# semaforo.net
KiCad netlist of a schematic drawn in EAGLE
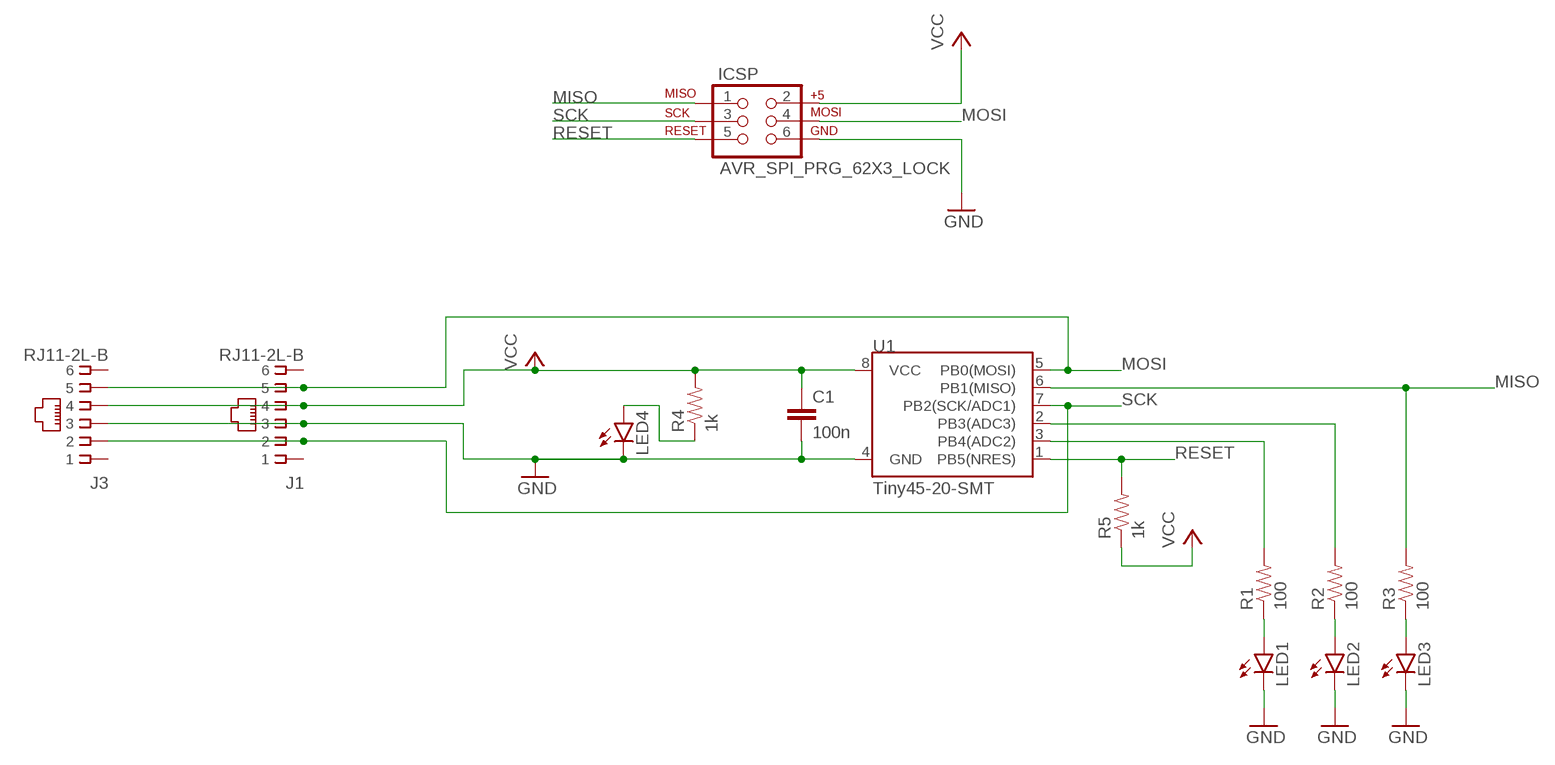
[diagram p0: schematic, sheet 1]

(export (version "E")
  (design (tool "Eeschema 10.0.6"))
  (components
    (comp (ref "C1")
      (value "100n")
      (footprint "eagle-import:1206")
      (libsource (lib "eagle-import") (part "CAP1206"))
    )
    (comp (ref "ICSP")
      (value "AVR_SPI_PRG_62X3_LOCK")
      (footprint "eagle-import:2X3_LOCK")
      (libsource (lib "eagle-import") (part "AVR_SPI_PRG_62X3_LOCK"))
    )
    (comp (ref "J1")
      (value "RJ11-2L-B")
      (footprint "eagle-import:RJ11-NO_SHIELD")
      (fields (field (name "MF") "TYCO ELECTRONICS"))
      (libsource (lib "eagle-import") (part "RJ11-2L-B"))
    )
    (comp (ref "J3")
      (value "RJ11-2L-B")
      (footprint "eagle-import:RJ11-NO_SHIELD")
      (fields (field (name "MF") "TYCO ELECTRONICS"))
      (libsource (lib "eagle-import") (part "RJ11-2L-B"))
    )
    (comp (ref "LED1")
      (value "LED5MM")
      (footprint "eagle-import:LED5MM")
      (libsource (lib "eagle-import") (part "LED5MM"))
    )
    (comp (ref "LED2")
      (value "LED5MM")
      (footprint "eagle-import:LED5MM")
      (libsource (lib "eagle-import") (part "LED5MM"))
    )
    (comp (ref "LED3")
      (value "LED5MM")
      (footprint "eagle-import:LED5MM")
      (libsource (lib "eagle-import") (part "LED5MM"))
    )
    (comp (ref "LED4")
      (value "LED1206")
      (footprint "eagle-import:LED-1206")
      (libsource (lib "eagle-import") (part "LED1206"))
    )
    (comp (ref "R1")
      (value "100")
      (footprint "eagle-import:1206")
      (libsource (lib "eagle-import") (part "RESISTOR1206"))
    )
    (comp (ref "R2")
      (value "100")
      (footprint "eagle-import:1206")
      (libsource (lib "eagle-import") (part "RESISTOR1206"))
    )
    (comp (ref "R3")
      (value "100")
      (footprint "eagle-import:1206")
      (libsource (lib "eagle-import") (part "RESISTOR1206"))
    )
    (comp (ref "R4")
      (value "1k")
      (footprint "eagle-import:1206")
      (libsource (lib "eagle-import") (part "RESISTOR1206"))
    )
    (comp (ref "R5")
      (value "1k")
      (footprint "eagle-import:1206")
      (libsource (lib "eagle-import") (part "RESISTOR1206"))
    )
    (comp (ref "U1")
      (value "Tiny45-20-SMT")
      (footprint "eagle-import:SO08-EIAJ")
      (libsource (lib "eagle-import") (part "ATTINY45TINY45-20-SMT"))
    )
  )
  (nets
    (net (code "1") (name "/MISO") (class "Default")
      (node (ref "ICSP") (pin "1") (pinfunction "1_1") (pintype "passive"))
      (node (ref "R3") (pin "2") (pinfunction "2_2") (pintype "passive"))
      (node (ref "U1") (pin "6") (pinfunction "PB1(MISO)_6") (pintype "bidirectional"))
    )
    (net (code "2") (name "/MOSI") (class "Default")
      (node (ref "ICSP") (pin "4") (pinfunction "4_4") (pintype "passive"))
      (node (ref "J1") (pin "5") (pinfunction "5_5") (pintype "passive"))
      (node (ref "J3") (pin "5") (pinfunction "5_5") (pintype "passive"))
      (node (ref "U1") (pin "5") (pinfunction "PB0(MOSI)_5") (pintype "bidirectional"))
    )
    (net (code "3") (name "/RESET") (class "Default")
      (node (ref "ICSP") (pin "5") (pinfunction "5_5") (pintype "passive"))
      (node (ref "R5") (pin "2") (pinfunction "2_2") (pintype "passive"))
      (node (ref "U1") (pin "1") (pinfunction "PB5(NRES)_1") (pintype "bidirectional"))
    )
    (net (code "4") (name "/SCK") (class "Default")
      (node (ref "ICSP") (pin "3") (pinfunction "3_3") (pintype "passive"))
      (node (ref "J1") (pin "2") (pinfunction "2_2") (pintype "passive"))
      (node (ref "J3") (pin "2") (pinfunction "2_2") (pintype "passive"))
      (node (ref "U1") (pin "7") (pinfunction "PB2(SCK/ADC1)_7") (pintype "bidirectional"))
    )
    (net (code "5") (name "GND") (class "Default")
      (node (ref "C1") (pin "2") (pinfunction "2_2") (pintype "passive"))
      (node (ref "ICSP") (pin "6") (pinfunction "6_6") (pintype "passive"))
      (node (ref "J1") (pin "3") (pinfunction "3_3") (pintype "passive"))
      (node (ref "J3") (pin "3") (pinfunction "3_3") (pintype "passive"))
      (node (ref "LED1") (pin "K") (pinfunction "C_K") (pintype "passive"))
      (node (ref "LED2") (pin "K") (pinfunction "C_K") (pintype "passive"))
      (node (ref "LED3") (pin "K") (pinfunction "C_K") (pintype "passive"))
      (node (ref "LED4") (pin "C") (pinfunction "C_C") (pintype "passive"))
      (node (ref "U1") (pin "4") (pinfunction "GND_4") (pintype "bidirectional"))
    )
    (net (code "6") (name "Net-(LED1-PadA)") (class "Default")
      (node (ref "LED1") (pin "A") (pinfunction "A_A") (pintype "passive"))
      (node (ref "R1") (pin "1") (pinfunction "1_1") (pintype "passive"))
    )
    (net (code "7") (name "Net-(LED2-PadA)") (class "Default")
      (node (ref "LED2") (pin "A") (pinfunction "A_A") (pintype "passive"))
      (node (ref "R2") (pin "1") (pinfunction "1_1") (pintype "passive"))
    )
    (net (code "8") (name "Net-(LED3-PadA)") (class "Default")
      (node (ref "LED3") (pin "A") (pinfunction "A_A") (pintype "passive"))
      (node (ref "R3") (pin "1") (pinfunction "1_1") (pintype "passive"))
    )
    (net (code "9") (name "Net-(LED4-PadA)") (class "Default")
      (node (ref "LED4") (pin "A") (pinfunction "A_A") (pintype "passive"))
      (node (ref "R4") (pin "1") (pinfunction "1_1") (pintype "passive"))
    )
    (net (code "10") (name "Net-(U1-PB3(ADC3))") (class "Default")
      (node (ref "R2") (pin "2") (pinfunction "2_2") (pintype "passive"))
      (node (ref "U1") (pin "2") (pinfunction "PB3(ADC3)_2") (pintype "bidirectional"))
    )
    (net (code "11") (name "Net-(U1-PB4(ADC2))") (class "Default")
      (node (ref "R1") (pin "2") (pinfunction "2_2") (pintype "passive"))
      (node (ref "U1") (pin "3") (pinfunction "PB4(ADC2)_3") (pintype "bidirectional"))
    )
    (net (code "12") (name "VCC") (class "Default")
      (node (ref "C1") (pin "1") (pinfunction "1_1") (pintype "passive"))
      (node (ref "ICSP") (pin "2") (pinfunction "2_2") (pintype "passive"))
      (node (ref "J1") (pin "4") (pinfunction "4_4") (pintype "passive"))
      (node (ref "J3") (pin "4") (pinfunction "4_4") (pintype "passive"))
      (node (ref "R4") (pin "2") (pinfunction "2_2") (pintype "passive"))
      (node (ref "R5") (pin "1") (pinfunction "1_1") (pintype "passive"))
      (node (ref "U1") (pin "8") (pinfunction "VCC_8") (pintype "bidirectional"))
    )
    (net (code "13") (name "unconnected-(J1-Pad1)") (class "Default")
      (node (ref "J1") (pin "1") (pinfunction "1_1") (pintype "passive"))
    )
    (net (code "14") (name "unconnected-(J1-Pad6)") (class "Default")
      (node (ref "J1") (pin "6") (pinfunction "6_6") (pintype "passive"))
    )
    (net (code "15") (name "unconnected-(J3-Pad1)") (class "Default")
      (node (ref "J3") (pin "1") (pinfunction "1_1") (pintype "passive"))
    )
    (net (code "16") (name "unconnected-(J3-Pad6)") (class "Default")
      (node (ref "J3") (pin "6") (pinfunction "6_6") (pintype "passive"))
    )
  )
)
